# logic_module.net
KiCad netlist of a schematic drawn in EAGLE
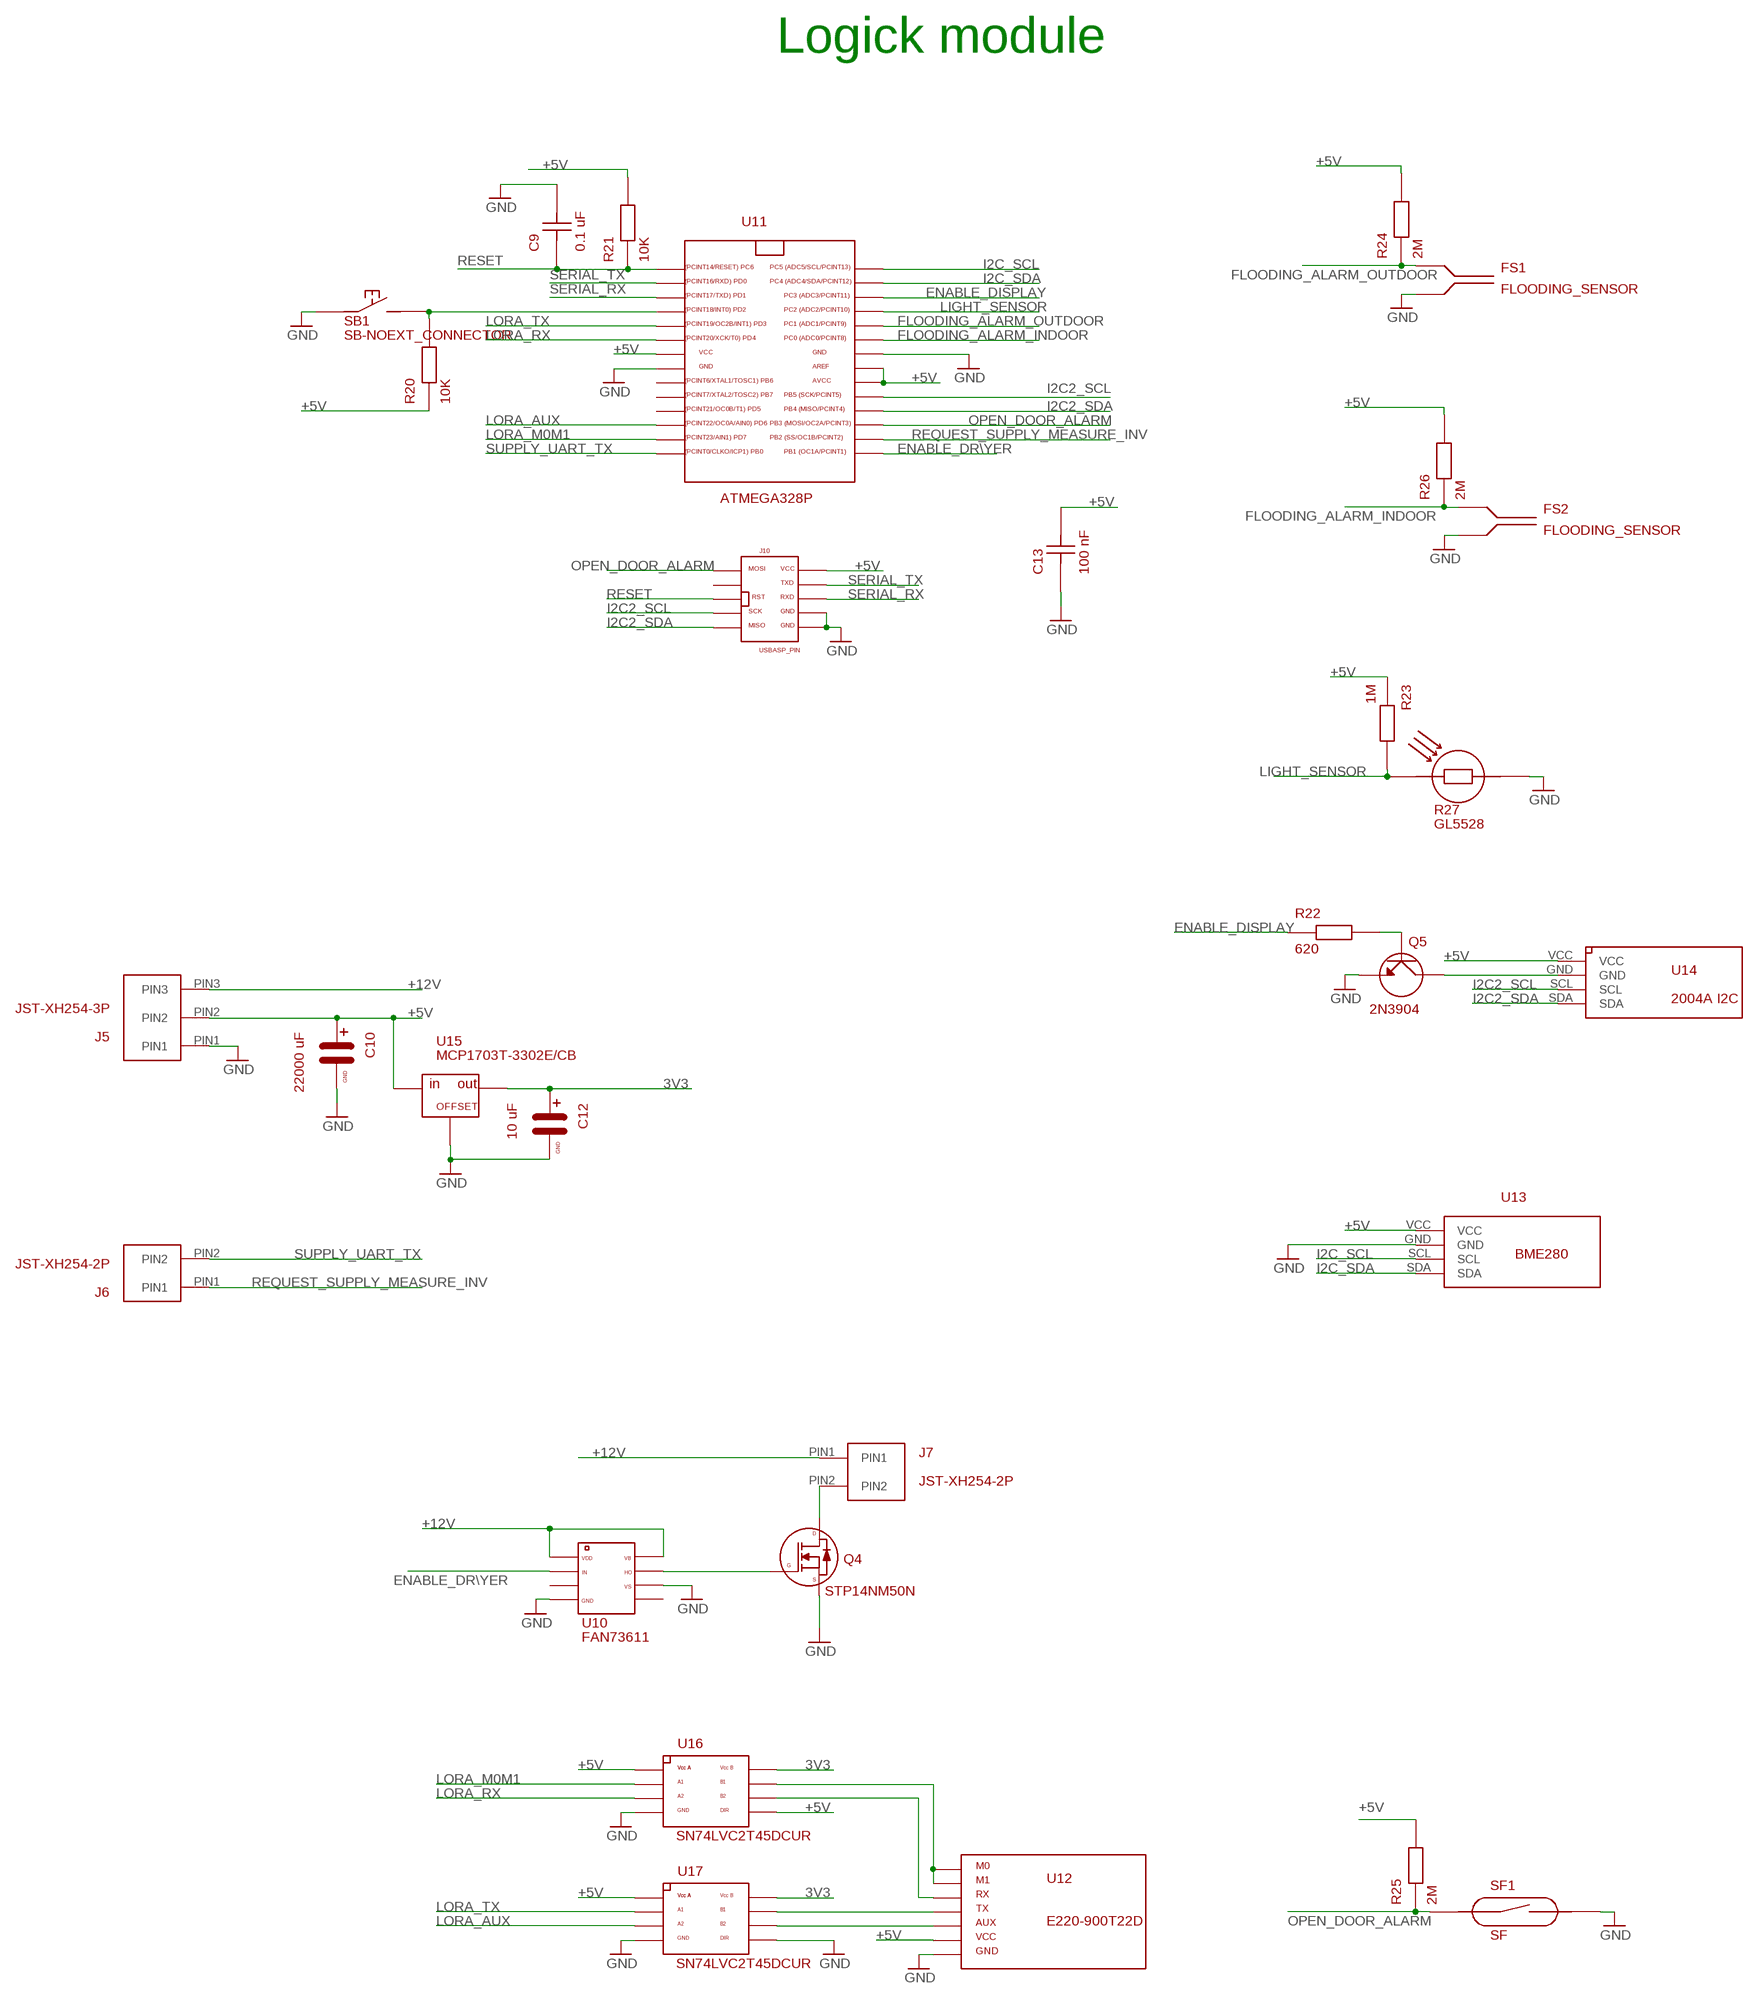
[diagram p0: schematic, sheet 1]

(export (version "E")
  (design (tool "Eeschema 10.0.6"))
  (components
    (comp (ref "C9")
      (value "0.1 uF")
      (footprint "eagle-import:C-1")
      (libsource (lib "eagle-import") (part "C-1"))
    )
    (comp (ref "C10")
      (value "22000 uF")
      (footprint "eagle-import:C-MINI-5X7")
      (libsource (lib "eagle-import") (part "CMINI-5X7"))
    )
    (comp (ref "C12")
      (value "10 uF")
      (footprint "eagle-import:C-MINI-5X7")
      (libsource (lib "eagle-import") (part "CMINI-5X7"))
    )
    (comp (ref "C13")
      (value "100 nF")
      (footprint "eagle-import:C-1")
      (libsource (lib "eagle-import") (part "C-1"))
    )
    (comp (ref "FS1")
      (value "FLOODING_SENSOR")
      (footprint "eagle-import:FLOODING_SENSOR")
      (libsource (lib "eagle-import") (part "FLOODING_SENSOR"))
    )
    (comp (ref "FS2")
      (value "FLOODING_SENSOR")
      (footprint "eagle-import:FLOODING_SENSOR")
      (libsource (lib "eagle-import") (part "FLOODING_SENSOR"))
    )
    (comp (ref "J5")
      (value "JST-XH254-3P")
      (footprint "eagle-import:JST-XH254-3P")
      (libsource (lib "eagle-import") (part "JST-XH254-3P"))
    )
    (comp (ref "J6")
      (value "JST-XH254-2P")
      (footprint "eagle-import:JST-XH254-2P")
      (libsource (lib "eagle-import") (part "JST-XH254-2P"))
    )
    (comp (ref "J7")
      (value "JST-XH254-2P")
      (footprint "eagle-import:JST-XH254-2P")
      (libsource (lib "eagle-import") (part "JST-XH254-2P"))
    )
    (comp (ref "J10")
      (value "USBASP_PIN")
      (footprint "eagle-import:USBASP_PIN")
      (libsource (lib "eagle-import") (part "USBASP_PIN"))
    )
    (comp (ref "Q4")
      (value "STP14NM50N")
      (footprint "eagle-import:MOSFET_N")
      (libsource (lib "eagle-import") (part "MOSFET_N"))
    )
    (comp (ref "Q5")
      (value "2N3904")
      (footprint "eagle-import:TRANSISTOR")
      (libsource (lib "eagle-import") (part "TRANSISTOR_NPN"))
    )
    (comp (ref "R20") (value "10K") (footprint "eagle-import:R") (libsource (lib "eagle-import") (part "R")))
    (comp (ref "R21") (value "10K") (footprint "eagle-import:R") (libsource (lib "eagle-import") (part "R")))
    (comp (ref "R22") (value "620") (footprint "eagle-import:R") (libsource (lib "eagle-import") (part "R")))
    (comp (ref "R23") (value "1M") (footprint "eagle-import:R") (libsource (lib "eagle-import") (part "R")))
    (comp (ref "R24") (value "2M") (footprint "eagle-import:R") (libsource (lib "eagle-import") (part "R")))
    (comp (ref "R25") (value "2M") (footprint "eagle-import:R") (libsource (lib "eagle-import") (part "R")))
    (comp (ref "R26") (value "2M") (footprint "eagle-import:R") (libsource (lib "eagle-import") (part "R")))
    (comp (ref "R27")
      (value "GL5528")
      (footprint "eagle-import:RF")
      (libsource (lib "eagle-import") (part "RF"))
    )
    (comp (ref "SB1")
      (value "SB-NOEXT_CONNECTOR")
      (footprint "eagle-import:SB-EXT")
      (libsource (lib "eagle-import") (part "SB-NOEXT_CONNECTOR"))
    )
    (comp (ref "SF1") (value "SF") (footprint "eagle-import:SF") (libsource (lib "eagle-import") (part "SF")))
    (comp (ref "U10")
      (value "FAN73611")
      (footprint "eagle-import:SOIC-8")
      (libsource (lib "eagle-import") (part "FAN73611"))
    )
    (comp (ref "U11")
      (value "ATMEGA328P")
      (footprint "eagle-import:ATMEGA328P")
      (libsource (lib "eagle-import") (part "ATMEGA328P"))
    )
    (comp (ref "U12")
      (value "E220-900T22D")
      (footprint "eagle-import:LORA")
      (libsource (lib "eagle-import") (part "LORA"))
    )
    (comp (ref "U13")
      (value "BME280BME280-CONNECTOR-ONLY")
      (footprint "eagle-import:BME280-CONNECTOR-ONLY")
      (libsource (lib "eagle-import") (part "BME280BME280-CONNECTOR-ONLY"))
    )
    (comp (ref "U14")
      (value "2004A I2C")
      (footprint "eagle-import:I2C_DISPLAY")
      (libsource (lib "eagle-import") (part "I2C_DISPLAY"))
    )
    (comp (ref "U15")
      (value "MCP1703T-3302E/CB")
      (footprint "eagle-import:SOT-23A")
      (libsource (lib "eagle-import") (part "VOLTAGE_REGULATORSOT-23A"))
    )
    (comp (ref "U16")
      (value "SN74LVC2T45DCUR")
      (footprint "eagle-import:VSSOP-8")
      (libsource (lib "eagle-import") (part "LEVEL_CONVERTER_2L"))
    )
    (comp (ref "U17")
      (value "SN74LVC2T45DCUR")
      (footprint "eagle-import:VSSOP-8")
      (libsource (lib "eagle-import") (part "LEVEL_CONVERTER_2L"))
    )
  )
  (nets
    (net (code "1") (name "/+5V") (class "Default")
      (node (ref "C10") (pin "PLUS") (pinfunction "PIN_PLUS_PLUS") (pintype "bidirectional"))
      (node (ref "C13") (pin "P$2") (pinfunction "P$2_P$2") (pintype "bidirectional"))
      (node (ref "J10") (pin "VCC") (pinfunction "VCC_VCC") (pintype "power_in"))
      (node (ref "J5") (pin "PIN2") (pinfunction "PIN2_PIN2") (pintype "bidirectional"))
      (node (ref "R20") (pin "P$1") (pinfunction "P$1_P$1") (pintype "bidirectional"))
      (node (ref "R21") (pin "P$2") (pinfunction "P$2_P$2") (pintype "bidirectional"))
      (node (ref "R23") (pin "P$1") (pinfunction "P$1_P$1") (pintype "bidirectional"))
      (node (ref "R24") (pin "P$2") (pinfunction "P$2_P$2") (pintype "bidirectional"))
      (node (ref "R25") (pin "P$2") (pinfunction "P$2_P$2") (pintype "bidirectional"))
      (node (ref "R26") (pin "P$2") (pinfunction "P$2_P$2") (pintype "bidirectional"))
      (node (ref "U11") (pin "AREF") (pinfunction "AREF_AREF") (pintype "bidirectional"))
      (node (ref "U11") (pin "AVCC") (pinfunction "AVCC_AVCC") (pintype "power_in"))
      (node (ref "U11") (pin "VCC") (pinfunction "VCC_VCC") (pintype "power_in"))
      (node (ref "U12") (pin "VCC") (pinfunction "VCC_VCC") (pintype "power_in"))
      (node (ref "U13") (pin "VCC") (pinfunction "VCC_VCC") (pintype "power_in"))
      (node (ref "U14") (pin "VCC") (pinfunction "VCC_VCC") (pintype "power_in"))
      (node (ref "U15") (pin "P3") (pinfunction "IN_P3") (pintype "power_in"))
      (node (ref "U16") (pin "P1") (pinfunction "VCCA_P1") (pintype "power_in"))
      (node (ref "U16") (pin "P5") (pinfunction "DIR_P5") (pintype "bidirectional"))
      (node (ref "U17") (pin "P1") (pinfunction "VCCA_P1") (pintype "power_in"))
    )
    (net (code "2") (name "/+12V") (class "Default")
      (node (ref "J5") (pin "PIN3") (pinfunction "PIN3_PIN3") (pintype "bidirectional"))
      (node (ref "J7") (pin "PIN1") (pinfunction "PIN1_PIN1") (pintype "bidirectional"))
      (node (ref "U10") (pin "P_1") (pinfunction "VDD_P_1") (pintype "power_in"))
      (node (ref "U10") (pin "P_8") (pinfunction "VB_P_8") (pintype "power_in"))
    )
    (net (code "3") (name "/3V3") (class "Default")
      (node (ref "C12") (pin "PLUS") (pinfunction "PIN_PLUS_PLUS") (pintype "bidirectional"))
      (node (ref "U15") (pin "P2") (pinfunction "OUT_P2") (pintype "power_in"))
      (node (ref "U16") (pin "P8") (pinfunction "VCCB_P8") (pintype "power_in"))
      (node (ref "U17") (pin "P8") (pinfunction "VCCB_P8") (pintype "power_in"))
    )
    (net (code "4") (name "/ENABLE_DISPLAY") (class "Default")
      (node (ref "R22") (pin "P$1") (pinfunction "P$1_P$1") (pintype "bidirectional"))
      (node (ref "U11") (pin "PC3") (pinfunction "PC3_PC3") (pintype "bidirectional"))
    )
    (net (code "5") (name "/ENABLE_DR\\YER") (class "Default")
      (node (ref "U10") (pin "P_2") (pinfunction "IN_P_2") (pintype "input"))
      (node (ref "U11") (pin "PB1") (pinfunction "PB1_PB1") (pintype "bidirectional"))
    )
    (net (code "6") (name "/FLOODING_ALARM_INDOOR") (class "Default")
      (node (ref "FS2") (pin "P$1") (pinfunction "P$1_P$1") (pintype "bidirectional"))
      (node (ref "R26") (pin "P$1") (pinfunction "P$1_P$1") (pintype "bidirectional"))
      (node (ref "U11") (pin "PC0") (pinfunction "PC0_PC0") (pintype "bidirectional"))
    )
    (net (code "7") (name "/FLOODING_ALARM_OUTDOOR") (class "Default")
      (node (ref "FS1") (pin "P$1") (pinfunction "P$1_P$1") (pintype "bidirectional"))
      (node (ref "R24") (pin "P$1") (pinfunction "P$1_P$1") (pintype "bidirectional"))
      (node (ref "U11") (pin "PC1") (pinfunction "PC1_PC1") (pintype "bidirectional"))
    )
    (net (code "8") (name "/I2C2_SCL") (class "Default")
      (node (ref "J10") (pin "SCK") (pinfunction "SCK_SCK") (pintype "bidirectional"))
      (node (ref "U11") (pin "PB5") (pinfunction "PB5_PB5") (pintype "bidirectional"))
      (node (ref "U14") (pin "SCL") (pinfunction "SCL_SCL") (pintype "bidirectional"))
    )
    (net (code "9") (name "/I2C2_SDA") (class "Default")
      (node (ref "J10") (pin "MISO") (pinfunction "MISO_MISO") (pintype "bidirectional"))
      (node (ref "U11") (pin "PB4") (pinfunction "PB4_PB4") (pintype "bidirectional"))
      (node (ref "U14") (pin "SDA") (pinfunction "SDA_SDA") (pintype "bidirectional"))
    )
    (net (code "10") (name "/I2C_SCL") (class "Default")
      (node (ref "U11") (pin "PC5") (pinfunction "PC5_PC5") (pintype "bidirectional"))
      (node (ref "U13") (pin "SCL") (pinfunction "SCL_SCL") (pintype "bidirectional"))
    )
    (net (code "11") (name "/I2C_SDA") (class "Default")
      (node (ref "U11") (pin "PC4") (pinfunction "PC4_PC4") (pintype "bidirectional"))
      (node (ref "U13") (pin "SDA") (pinfunction "SDA_SDA") (pintype "bidirectional"))
    )
    (net (code "12") (name "/LIGHT_SENSOR") (class "Default")
      (node (ref "R23") (pin "P$2") (pinfunction "P$2_P$2") (pintype "bidirectional"))
      (node (ref "R27") (pin "PIN1") (pinfunction "P$1_PIN1") (pintype "bidirectional"))
      (node (ref "U11") (pin "PC2") (pinfunction "PC2_PC2") (pintype "bidirectional"))
    )
    (net (code "13") (name "/LORA_AUX") (class "Default")
      (node (ref "U11") (pin "PD6") (pinfunction "PD6_PD6") (pintype "bidirectional"))
      (node (ref "U17") (pin "P3") (pinfunction "A2_P3") (pintype "bidirectional"))
    )
    (net (code "14") (name "/LORA_M0M1") (class "Default")
      (node (ref "U11") (pin "PD7") (pinfunction "PD7_PD7") (pintype "bidirectional"))
      (node (ref "U16") (pin "P2") (pinfunction "A1_P2") (pintype "bidirectional"))
    )
    (net (code "15") (name "/LORA_RX") (class "Default")
      (node (ref "U11") (pin "PD4") (pinfunction "PD4_PD4") (pintype "bidirectional"))
      (node (ref "U16") (pin "P3") (pinfunction "A2_P3") (pintype "bidirectional"))
    )
    (net (code "16") (name "/LORA_TX") (class "Default")
      (node (ref "U11") (pin "PD3") (pinfunction "PD3_PD3") (pintype "bidirectional"))
      (node (ref "U17") (pin "P2") (pinfunction "A1_P2") (pintype "bidirectional"))
    )
    (net (code "17") (name "/OPEN_DOOR_ALARM") (class "Default")
      (node (ref "J10") (pin "MOSI") (pinfunction "MOSI_MOSI") (pintype "bidirectional"))
      (node (ref "R25") (pin "P$1") (pinfunction "P$1_P$1") (pintype "bidirectional"))
      (node (ref "SF1") (pin "P$1") (pinfunction "P$1_P$1") (pintype "bidirectional"))
      (node (ref "U11") (pin "PB3") (pinfunction "PB3_PB3") (pintype "bidirectional"))
    )
    (net (code "18") (name "/REQUEST_SUPPLY_MEASURE_INV") (class "Default")
      (node (ref "J6") (pin "PIN1") (pinfunction "PIN1_PIN1") (pintype "bidirectional"))
      (node (ref "U11") (pin "PB2") (pinfunction "PB2_PB2") (pintype "bidirectional"))
    )
    (net (code "19") (name "/RESET") (class "Default")
      (node (ref "C9") (pin "P$1") (pinfunction "P$1_P$1") (pintype "bidirectional"))
      (node (ref "J10") (pin "RST") (pinfunction "RESET_RST") (pintype "bidirectional"))
      (node (ref "R21") (pin "P$1") (pinfunction "P$1_P$1") (pintype "bidirectional"))
      (node (ref "U11") (pin "PC6") (pinfunction "PC6_PC6") (pintype "bidirectional"))
    )
    (net (code "20") (name "/SERIAL_RX") (class "Default")
      (node (ref "J10") (pin "RXD") (pinfunction "RXD_RXD") (pintype "bidirectional"))
      (node (ref "U11") (pin "PD1") (pinfunction "PD1_PD1") (pintype "bidirectional"))
    )
    (net (code "21") (name "/SERIAL_TX") (class "Default")
      (node (ref "J10") (pin "TXD") (pinfunction "TXD_TXD") (pintype "bidirectional"))
      (node (ref "U11") (pin "PD0") (pinfunction "PD0_PD0") (pintype "bidirectional"))
    )
    (net (code "22") (name "/SUPPLY_UART_TX") (class "Default")
      (node (ref "J6") (pin "PIN2") (pinfunction "PIN2_PIN2") (pintype "bidirectional"))
      (node (ref "U11") (pin "PB0") (pinfunction "PB0_PB0") (pintype "bidirectional"))
    )
    (net (code "23") (name "GND") (class "Default")
      (node (ref "C10") (pin "MINUS") (pinfunction "PIN_GND_MINUS") (pintype "bidirectional"))
      (node (ref "C12") (pin "MINUS") (pinfunction "PIN_GND_MINUS") (pintype "bidirectional"))
      (node (ref "C13") (pin "P$1") (pinfunction "P$1_P$1") (pintype "bidirectional"))
      (node (ref "C9") (pin "P$2") (pinfunction "P$2_P$2") (pintype "bidirectional"))
      (node (ref "FS1") (pin "P$2") (pinfunction "P$2_P$2") (pintype "bidirectional"))
      (node (ref "FS2") (pin "P$2") (pinfunction "P$2_P$2") (pintype "bidirectional"))
      (node (ref "J10") (pin "GND") (pinfunction "GND_GND") (pintype "power_in"))
      (node (ref "J10") (pin "GND1") (pinfunction "GND1_GND1") (pintype "power_in"))
      (node (ref "J5") (pin "PIN1") (pinfunction "PIN1_PIN1") (pintype "bidirectional"))
      (node (ref "Q4") (pin "S") (pinfunction "S_S") (pintype "bidirectional"))
      (node (ref "Q5") (pin "E") (pinfunction "E_E") (pintype "bidirectional"))
      (node (ref "R27") (pin "PIN2") (pinfunction "P$2_PIN2") (pintype "bidirectional"))
      (node (ref "SB1") (pin "P$1") (pinfunction "P$1_P$1") (pintype "bidirectional"))
      (node (ref "SF1") (pin "P$2") (pinfunction "P$2_P$2") (pintype "bidirectional"))
      (node (ref "U10") (pin "P_4") (pinfunction "GND_P_4") (pintype "power_in"))
      (node (ref "U10") (pin "P_6") (pinfunction "VS_P_6") (pintype "input"))
      (node (ref "U11") (pin "GND") (pinfunction "GND_GND") (pintype "power_in"))
      (node (ref "U11") (pin "GND1") (pinfunction "GND1_GND1") (pintype "power_in"))
      (node (ref "U12") (pin "GND") (pinfunction "GND_GND") (pintype "power_in"))
      (node (ref "U13") (pin "GND") (pinfunction "GND_GND") (pintype "power_in"))
      (node (ref "U15") (pin "P1") (pinfunction "GND_P1") (pintype "power_in"))
      (node (ref "U16") (pin "P4") (pinfunction "GND_P4") (pintype "power_in"))
      (node (ref "U17") (pin "P4") (pinfunction "GND_P4") (pintype "power_in"))
      (node (ref "U17") (pin "P5") (pinfunction "DIR_P5") (pintype "bidirectional"))
    )
    (net (code "24") (name "Net-(J7-PadPIN2)") (class "Default")
      (node (ref "J7") (pin "PIN2") (pinfunction "PIN2_PIN2") (pintype "bidirectional"))
      (node (ref "Q4") (pin "D") (pinfunction "D_D") (pintype "bidirectional"))
    )
    (net (code "25") (name "Net-(Q5-PadB)") (class "Default")
      (node (ref "Q5") (pin "B") (pinfunction "B_B") (pintype "bidirectional"))
      (node (ref "R22") (pin "P$2") (pinfunction "P$2_P$2") (pintype "bidirectional"))
    )
    (net (code "26") (name "Net-(Q5-PadC)") (class "Default")
      (node (ref "Q5") (pin "C") (pinfunction "C_C") (pintype "bidirectional"))
      (node (ref "U14") (pin "GND") (pinfunction "GND_GND") (pintype "power_in"))
    )
    (net (code "27") (name "Net-(R20-PadP$2)") (class "Default")
      (node (ref "R20") (pin "P$2") (pinfunction "P$2_P$2") (pintype "bidirectional"))
      (node (ref "SB1") (pin "P$2") (pinfunction "P$2_P$2") (pintype "bidirectional"))
      (node (ref "U11") (pin "PD2") (pinfunction "PD2_PD2") (pintype "bidirectional"))
    )
    (net (code "28") (name "Net-(U10-HO)") (class "Default")
      (node (ref "Q4") (pin "G") (pinfunction "G_G") (pintype "bidirectional"))
      (node (ref "U10") (pin "P_7") (pinfunction "HO_P_7") (pintype "output"))
    )
    (net (code "29") (name "Net-(U16-B1)") (class "Default")
      (node (ref "U12") (pin "M0") (pinfunction "M0_M0") (pintype "bidirectional"))
      (node (ref "U12") (pin "M1") (pinfunction "M1_M1") (pintype "bidirectional"))
      (node (ref "U16") (pin "P7") (pinfunction "B1_P7") (pintype "bidirectional"))
    )
    (net (code "30") (name "Net-(U16-B2)") (class "Default")
      (node (ref "U12") (pin "RX") (pinfunction "RX_RX") (pintype "bidirectional"))
      (node (ref "U16") (pin "P6") (pinfunction "B2_P6") (pintype "bidirectional"))
    )
    (net (code "31") (name "Net-(U17-B1)") (class "Default")
      (node (ref "U12") (pin "TX") (pinfunction "TX_TX") (pintype "bidirectional"))
      (node (ref "U17") (pin "P7") (pinfunction "B1_P7") (pintype "bidirectional"))
    )
    (net (code "32") (name "Net-(U17-B2)") (class "Default")
      (node (ref "U12") (pin "AUX") (pinfunction "AUX_AUX") (pintype "bidirectional"))
      (node (ref "U17") (pin "P6") (pinfunction "B2_P6") (pintype "bidirectional"))
    )
    (net (code "33") (name "unconnected-(J10-PadNC1)") (class "Default")
      (node (ref "J10") (pin "NC1") (pinfunction "NC1_NC1") (pintype "no_connect"))
    )
    (net (code "34") (name "unconnected-(U10-NC1-PadP_3)") (class "Default")
      (node (ref "U10") (pin "P_3") (pinfunction "NC1_P_3") (pintype "no_connect"))
    )
    (net (code "35") (name "unconnected-(U10-NC2-PadP_5)") (class "Default")
      (node (ref "U10") (pin "P_5") (pinfunction "NC2_P_5") (pintype "no_connect"))
    )
    (net (code "36") (name "unconnected-(U11-PadPB6)") (class "Default")
      (node (ref "U11") (pin "PB6") (pinfunction "PB6_PB6") (pintype "bidirectional"))
    )
    (net (code "37") (name "unconnected-(U11-PadPB7)") (class "Default")
      (node (ref "U11") (pin "PB7") (pinfunction "PB7_PB7") (pintype "bidirectional"))
    )
    (net (code "38") (name "unconnected-(U11-PadPD5)") (class "Default")
      (node (ref "U11") (pin "PD5") (pinfunction "PD5_PD5") (pintype "bidirectional"))
    )
  )
)
